# CM4_HighSpeed.net
KiCad netlist of a schematic drawn in Altium Designer
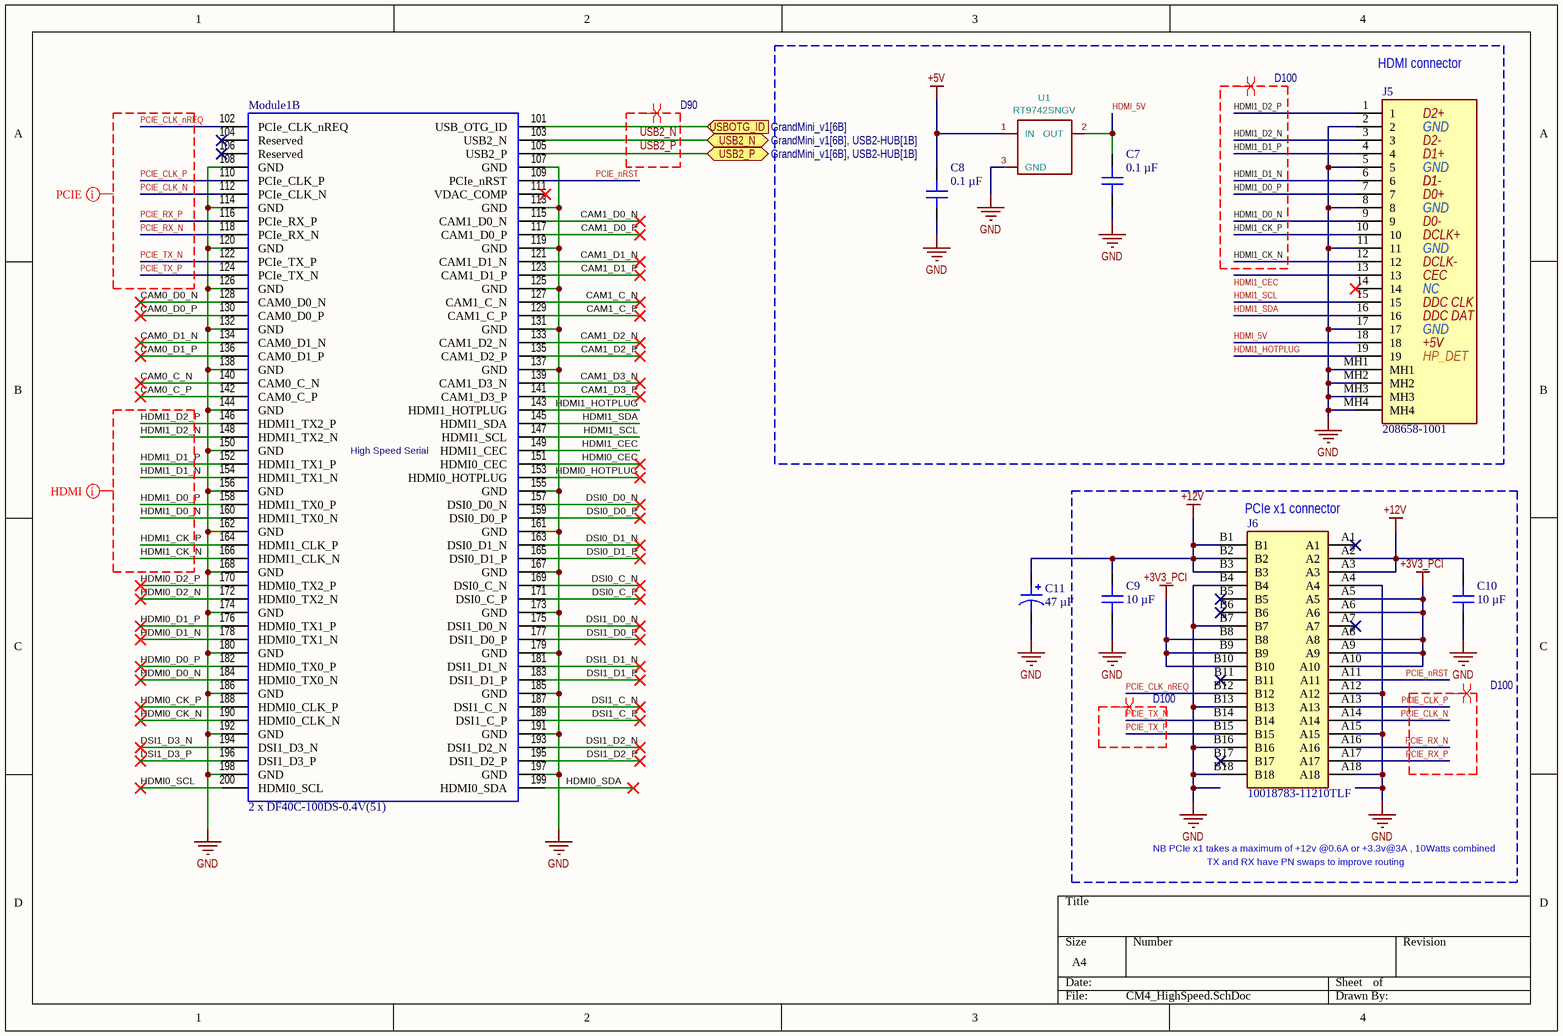
[diagram p0: CM4_HighSpeed.SchDoc]

(export (version "E")
  (design (tool "Eeschema 10.0.6"))
  (components
    (comp (ref "C7")
      (value "0.1 µF")
      (footprint "CAP 0603_1608")
      (description "CAP CER 0.1UF 50V X7R 0603")
      (fields (field (name "PART NUMBER") "CC0603KRX7R9BB104") (field (name "MANUFACTURER") "Yageo"))
      (libsource (lib "Celestial Altium Library - altium_library") (part "Capacitor"))
    )
    (comp (ref "C8")
      (value "0.1 µF")
      (footprint "CAP 0603_1608")
      (description "CAP CER 0.1UF 50V X7R 0603")
      (fields (field (name "PART NUMBER") "CC0603KRX7R9BB104") (field (name "MANUFACTURER") "Yageo"))
      (libsource (lib "Celestial Altium Library - altium_library") (part "Capacitor"))
    )
    (comp (ref "C9")
      (value "10 µF")
      (footprint "CAP 0805_2012")
      (description "CAP CER 10UF 25V X5R 0805")
      (fields (field (name "PART NUMBER") "CC0805KKX5R8BB106") (field (name "MANUFACTURER") "Yageo"))
      (libsource (lib "Celestial Altium Library - altium_library") (part "Capacitor"))
    )
    (comp (ref "C10")
      (value "10 µF")
      (footprint "CAP 0805_2012")
      (description "CAP CER 10UF 25V X5R 0805")
      (fields (field (name "PART NUMBER") "CC0805KKX5R8BB106") (field (name "MANUFACTURER") "Yageo"))
      (libsource (lib "Celestial Altium Library - altium_library") (part "Capacitor"))
    )
    (comp (ref "C11")
      (value "47 µF")
      (footprint "CAP POL 2917_7343")
      (description "CAP TANT 47UF 10% 35V 2917")
      (fields (field (name "PART NUMBER") "T491X476K035AT") (field (name "MANUFACTURER") "KEMET"))
      (libsource (lib "Celestial Altium Library - altium_library") (part "Polarised Capacitor"))
    )
    (comp (ref "J5")
      (value "208658-1001")
      (footprint "SamacSys:2086581001")
      (description "Connector, HDMI")
      (fields (field (name "MOUSER PART NUMBER") "538-208658-1001"))
      (libsource (lib "SamacSys") (part "208658-1001"))
    )
    (comp (ref "J6")
      (value "10018783-11210TLF")
      (footprint "SamacSys:1001878311210TLF")
      (description "Connector PCI-E")
      (libsource (lib "SamacSys") (part "10018783-11210TLF"))
    )
    (comp (ref "Module1")
      (value "2 x DF40C-100DS-0.4V(51)")
      (footprint "RPI_CM4_STACKED")
      (description "Rapsberry PI Compute Module 4 +")
      (libsource (lib "SamacSys") (part "RPi_CM4_1"))
    )
    (comp (ref "U1") (value "RT9742SNGV") (footprint "SOT-23") (libsource (lib "CM4IO") (part "RT9742SNGV")))
  )
  (nets
    (net (code "1") (name "+3V3_PCI") (class "Default")
      (node (ref "J6") (pin "A10") (pinfunction "A10_A10") (pintype "passive"))
      (node (ref "J6") (pin "A5") (pinfunction "A5_A5") (pintype "passive"))
      (node (ref "J6") (pin "A6") (pinfunction "A6_A6") (pintype "passive"))
      (node (ref "J6") (pin "A8") (pinfunction "A8_A8") (pintype "passive"))
      (node (ref "J6") (pin "A9") (pinfunction "A9_A9") (pintype "passive"))
      (node (ref "J6") (pin "B10") (pinfunction "B10_B10") (pintype "passive"))
      (node (ref "J6") (pin "B8") (pinfunction "B8_B8") (pintype "passive"))
      (node (ref "J6") (pin "B9") (pinfunction "B9_B9") (pintype "passive"))
    )
    (net (code "2") (name "+5V") (class "Default")
      (node (ref "C8") (pin "2") (pinfunction "2_2") (pintype "passive"))
      (node (ref "U1") (pin "1") (pinfunction "IN_1") (pintype "passive"))
    )
    (net (code "3") (name "+12V") (class "Default")
      (node (ref "C10") (pin "2") (pinfunction "2_2") (pintype "passive"))
      (node (ref "C11") (pin "1") (pinfunction "1_1") (pintype "passive"))
      (node (ref "C9") (pin "2") (pinfunction "2_2") (pintype "passive"))
      (node (ref "J6") (pin "A2") (pinfunction "A2_A2") (pintype "passive"))
      (node (ref "J6") (pin "A3") (pinfunction "A3_A3") (pintype "passive"))
      (node (ref "J6") (pin "B1") (pinfunction "B1_B1") (pintype "passive"))
      (node (ref "J6") (pin "B2") (pinfunction "B2_B2") (pintype "passive"))
      (node (ref "J6") (pin "B3") (pinfunction "B3_B3") (pintype "passive"))
    )
    (net (code "4") (name "/CAM0_C_N") (class "Default")
      (node (ref "Module1") (pin "140") (pinfunction "CAM0_C_N_140") (pintype "passive+no_connect"))
    )
    (net (code "5") (name "/CAM0_C_P") (class "Default")
      (node (ref "Module1") (pin "142") (pinfunction "CAM0_C_P_142") (pintype "passive+no_connect"))
    )
    (net (code "6") (name "/CAM0_D0_N") (class "Default")
      (node (ref "Module1") (pin "128") (pinfunction "CAM0_D0_N_128") (pintype "passive+no_connect"))
    )
    (net (code "7") (name "/CAM0_D0_P") (class "Default")
      (node (ref "Module1") (pin "130") (pinfunction "CAM0_D0_P_130") (pintype "passive+no_connect"))
    )
    (net (code "8") (name "/CAM0_D1_N") (class "Default")
      (node (ref "Module1") (pin "134") (pinfunction "CAM0_D1_N_134") (pintype "passive+no_connect"))
    )
    (net (code "9") (name "/CAM0_D1_P") (class "Default")
      (node (ref "Module1") (pin "136") (pinfunction "CAM0_D1_P_136") (pintype "passive+no_connect"))
    )
    (net (code "10") (name "/CAM1_C_N") (class "Default")
      (node (ref "Module1") (pin "127") (pinfunction "CAM1_C_N_127") (pintype "passive+no_connect"))
    )
    (net (code "11") (name "/CAM1_C_P") (class "Default")
      (node (ref "Module1") (pin "129") (pinfunction "CAM1_C_P_129") (pintype "passive+no_connect"))
    )
    (net (code "12") (name "/CAM1_D0_N") (class "Default")
      (node (ref "Module1") (pin "115") (pinfunction "CAM1_D0_N_115") (pintype "passive+no_connect"))
    )
    (net (code "13") (name "/CAM1_D0_P") (class "Default")
      (node (ref "Module1") (pin "117") (pinfunction "CAM1_D0_P_117") (pintype "passive+no_connect"))
    )
    (net (code "14") (name "/CAM1_D1_N") (class "Default")
      (node (ref "Module1") (pin "121") (pinfunction "CAM1_D1_N_121") (pintype "passive+no_connect"))
    )
    (net (code "15") (name "/CAM1_D1_P") (class "Default")
      (node (ref "Module1") (pin "123") (pinfunction "CAM1_D1_P_123") (pintype "passive+no_connect"))
    )
    (net (code "16") (name "/CAM1_D2_N") (class "Default")
      (node (ref "Module1") (pin "133") (pinfunction "CAM1_D2_N_133") (pintype "passive+no_connect"))
    )
    (net (code "17") (name "/CAM1_D2_P") (class "Default")
      (node (ref "Module1") (pin "135") (pinfunction "CAM1_D2_P_135") (pintype "passive+no_connect"))
    )
    (net (code "18") (name "/CAM1_D3_N") (class "Default")
      (node (ref "Module1") (pin "139") (pinfunction "CAM1_D3_N_139") (pintype "passive+no_connect"))
    )
    (net (code "19") (name "/CAM1_D3_P") (class "Default")
      (node (ref "Module1") (pin "141") (pinfunction "CAM1_D3_P_141") (pintype "passive+no_connect"))
    )
    (net (code "20") (name "/DSI0_C_N") (class "Default")
      (node (ref "Module1") (pin "169") (pinfunction "DSI0_C_N_169") (pintype "passive+no_connect"))
    )
    (net (code "21") (name "/DSI0_C_P") (class "Default")
      (node (ref "Module1") (pin "171") (pinfunction "DSI0_C_P_171") (pintype "passive+no_connect"))
    )
    (net (code "22") (name "/DSI0_D0_N") (class "Default")
      (node (ref "Module1") (pin "157") (pinfunction "DSI0_D0_N_157") (pintype "passive+no_connect"))
    )
    (net (code "23") (name "/DSI0_D0_P") (class "Default")
      (node (ref "Module1") (pin "159") (pinfunction "DSI0_D0_P_159") (pintype "passive+no_connect"))
    )
    (net (code "24") (name "/DSI0_D1_N") (class "Default")
      (node (ref "Module1") (pin "163") (pinfunction "DSI0_D1_N_163") (pintype "passive+no_connect"))
    )
    (net (code "25") (name "/DSI0_D1_P") (class "Default")
      (node (ref "Module1") (pin "165") (pinfunction "DSI0_D1_P_165") (pintype "passive+no_connect"))
    )
    (net (code "26") (name "/DSI1_C_N") (class "Default")
      (node (ref "Module1") (pin "187") (pinfunction "DSI1_C_N_187") (pintype "passive+no_connect"))
    )
    (net (code "27") (name "/DSI1_C_P") (class "Default")
      (node (ref "Module1") (pin "189") (pinfunction "DSI1_C_P_189") (pintype "passive+no_connect"))
    )
    (net (code "28") (name "/DSI1_D0_N") (class "Default")
      (node (ref "Module1") (pin "175") (pinfunction "DSI1_D0_N_175") (pintype "passive+no_connect"))
    )
    (net (code "29") (name "/DSI1_D0_P") (class "Default")
      (node (ref "Module1") (pin "177") (pinfunction "DSI1_D0_P_177") (pintype "passive+no_connect"))
    )
    (net (code "30") (name "/DSI1_D1_N") (class "Default")
      (node (ref "Module1") (pin "181") (pinfunction "DSI1_D1_N_181") (pintype "passive+no_connect"))
    )
    (net (code "31") (name "/DSI1_D1_P") (class "Default")
      (node (ref "Module1") (pin "183") (pinfunction "DSI1_D1_P_183") (pintype "passive+no_connect"))
    )
    (net (code "32") (name "/DSI1_D2_N") (class "Default")
      (node (ref "Module1") (pin "193") (pinfunction "DSI1_D2_N_193") (pintype "passive+no_connect"))
    )
    (net (code "33") (name "/DSI1_D2_P") (class "Default")
      (node (ref "Module1") (pin "195") (pinfunction "DSI1_D2_P_195") (pintype "passive+no_connect"))
    )
    (net (code "34") (name "/DSI1_D3_N") (class "Default")
      (node (ref "Module1") (pin "194") (pinfunction "DSI1_D3_N_194") (pintype "passive+no_connect"))
    )
    (net (code "35") (name "/DSI1_D3_P") (class "Default")
      (node (ref "Module1") (pin "196") (pinfunction "DSI1_D3_P_196") (pintype "passive+no_connect"))
    )
    (net (code "36") (name "/HDMI0_CEC") (class "Default")
      (node (ref "Module1") (pin "151") (pinfunction "HDMI0_CEC_151") (pintype "passive+no_connect"))
    )
    (net (code "37") (name "/HDMI0_CK_N") (class "Default")
      (node (ref "Module1") (pin "190") (pinfunction "HDMI0_CLK_N_190") (pintype "passive+no_connect"))
    )
    (net (code "38") (name "/HDMI0_CK_P") (class "Default")
      (node (ref "Module1") (pin "188") (pinfunction "HDMI0_CLK_P_188") (pintype "passive+no_connect"))
    )
    (net (code "39") (name "/HDMI0_D0_N") (class "Default")
      (node (ref "Module1") (pin "184") (pinfunction "HDMI0_TX0_N_184") (pintype "passive+no_connect"))
    )
    (net (code "40") (name "/HDMI0_D0_P") (class "Default")
      (node (ref "Module1") (pin "182") (pinfunction "HDMI0_TX0_P_182") (pintype "passive+no_connect"))
    )
    (net (code "41") (name "/HDMI0_D1_N") (class "Default")
      (node (ref "Module1") (pin "178") (pinfunction "HDMI0_TX1_N_178") (pintype "passive+no_connect"))
    )
    (net (code "42") (name "/HDMI0_D1_P") (class "Default")
      (node (ref "Module1") (pin "176") (pinfunction "HDMI0_TX1_P_176") (pintype "passive+no_connect"))
    )
    (net (code "43") (name "/HDMI0_D2_N") (class "Default")
      (node (ref "Module1") (pin "172") (pinfunction "HDMI0_TX2_N_172") (pintype "passive+no_connect"))
    )
    (net (code "44") (name "/HDMI0_D2_P") (class "Default")
      (node (ref "Module1") (pin "170") (pinfunction "HDMI0_TX2_P_170") (pintype "passive+no_connect"))
    )
    (net (code "45") (name "/HDMI0_HOTPLUG") (class "Default")
      (node (ref "Module1") (pin "153") (pinfunction "HDMI0_HOTPLUG_153") (pintype "passive+no_connect"))
    )
    (net (code "46") (name "/HDMI0_SCL") (class "Default")
      (node (ref "Module1") (pin "200") (pinfunction "HDMI0_SCL_200") (pintype "passive+no_connect"))
    )
    (net (code "47") (name "/HDMI0_SDA") (class "Default")
      (node (ref "Module1") (pin "199") (pinfunction "HDMI0_SDA_199") (pintype "passive+no_connect"))
    )
    (net (code "48") (name "/HDMI1_CEC") (class "Default")
      (node (ref "J5") (pin "13") (pinfunction "13_13") (pintype "passive"))
      (node (ref "Module1") (pin "149") (pinfunction "HDMI1_CEC_149") (pintype "passive"))
    )
    (net (code "49") (name "/HDMI1_CK_N") (class "Default")
      (node (ref "J5") (pin "12") (pinfunction "12_12") (pintype "passive"))
      (node (ref "Module1") (pin "166") (pinfunction "HDMI1_CLK_N_166") (pintype "passive"))
    )
    (net (code "50") (name "/HDMI1_CK_P") (class "Default")
      (node (ref "J5") (pin "10") (pinfunction "10_10") (pintype "passive"))
      (node (ref "Module1") (pin "164") (pinfunction "HDMI1_CLK_P_164") (pintype "passive"))
    )
    (net (code "51") (name "/HDMI1_D0_N") (class "Default")
      (node (ref "J5") (pin "9") (pinfunction "9_9") (pintype "passive"))
      (node (ref "Module1") (pin "160") (pinfunction "HDMI1_TX0_N_160") (pintype "passive"))
    )
    (net (code "52") (name "/HDMI1_D0_P") (class "Default")
      (node (ref "J5") (pin "7") (pinfunction "7_7") (pintype "passive"))
      (node (ref "Module1") (pin "158") (pinfunction "HDMI1_TX0_P_158") (pintype "passive"))
    )
    (net (code "53") (name "/HDMI1_D1_N") (class "Default")
      (node (ref "J5") (pin "6") (pinfunction "6_6") (pintype "passive"))
      (node (ref "Module1") (pin "154") (pinfunction "HDMI1_TX1_N_154") (pintype "passive"))
    )
    (net (code "54") (name "/HDMI1_D1_P") (class "Default")
      (node (ref "J5") (pin "4") (pinfunction "4_4") (pintype "passive"))
      (node (ref "Module1") (pin "152") (pinfunction "HDMI1_TX1_P_152") (pintype "passive"))
    )
    (net (code "55") (name "/HDMI1_D2_N") (class "Default")
      (node (ref "J5") (pin "3") (pinfunction "3_3") (pintype "passive"))
      (node (ref "Module1") (pin "148") (pinfunction "HDMI1_TX2_N_148") (pintype "passive"))
    )
    (net (code "56") (name "/HDMI1_D2_P") (class "Default")
      (node (ref "J5") (pin "1") (pinfunction "1_1") (pintype "passive"))
      (node (ref "Module1") (pin "146") (pinfunction "HDMI1_TX2_P_146") (pintype "passive"))
    )
    (net (code "57") (name "/HDMI1_HOTPLUG") (class "Default")
      (node (ref "J5") (pin "19") (pinfunction "19_19") (pintype "passive"))
      (node (ref "Module1") (pin "143") (pinfunction "HDMI1_HOTPLUG_143") (pintype "passive"))
    )
    (net (code "58") (name "/HDMI1_SCL") (class "Default")
      (node (ref "J5") (pin "15") (pinfunction "15_15") (pintype "passive"))
      (node (ref "Module1") (pin "147") (pinfunction "HDMI1_SCL_147") (pintype "passive"))
    )
    (net (code "59") (name "/HDMI1_SDA") (class "Default")
      (node (ref "J5") (pin "16") (pinfunction "16_16") (pintype "passive"))
      (node (ref "Module1") (pin "145") (pinfunction "HDMI1_SDA_145") (pintype "passive"))
    )
    (net (code "60") (name "/HDMI_5V") (class "Default")
      (node (ref "C7") (pin "2") (pinfunction "2_2") (pintype "passive"))
      (node (ref "J5") (pin "18") (pinfunction "18_18") (pintype "passive"))
      (node (ref "U1") (pin "2") (pinfunction "OUT_2") (pintype "passive"))
    )
    (net (code "61") (name "/PCIE_CLK_N") (class "Default")
      (node (ref "J6") (pin "A14") (pinfunction "A14_A14") (pintype "passive"))
      (node (ref "Module1") (pin "112") (pinfunction "PCIe_CLK_N_112") (pintype "passive"))
    )
    (net (code "62") (name "/PCIE_CLK_P") (class "Default")
      (node (ref "J6") (pin "A13") (pinfunction "A13_A13") (pintype "passive"))
      (node (ref "Module1") (pin "110") (pinfunction "PCIe_CLK_P_110") (pintype "passive"))
    )
    (net (code "63") (name "/PCIE_CLK_nREQ") (class "Default")
      (node (ref "J6") (pin "B12") (pinfunction "B12_B12") (pintype "passive"))
      (node (ref "Module1") (pin "102") (pinfunction "PCIe_CLK_nREQ_102") (pintype "passive"))
    )
    (net (code "64") (name "/PCIE_RX_N") (class "Default")
      (node (ref "J6") (pin "A16") (pinfunction "A16_A16") (pintype "passive"))
      (node (ref "Module1") (pin "118") (pinfunction "PCIe_RX_N_118") (pintype "passive"))
    )
    (net (code "65") (name "/PCIE_RX_P") (class "Default")
      (node (ref "J6") (pin "A17") (pinfunction "A17_A17") (pintype "passive"))
      (node (ref "Module1") (pin "116") (pinfunction "PCIe_RX_P_116") (pintype "passive"))
    )
    (net (code "66") (name "/PCIE_TX_N") (class "Default")
      (node (ref "J6") (pin "B14") (pinfunction "B14_B14") (pintype "passive"))
      (node (ref "Module1") (pin "122") (pinfunction "PCIe_TX_P_122") (pintype "passive"))
    )
    (net (code "67") (name "/PCIE_TX_P") (class "Default")
      (node (ref "J6") (pin "B15") (pinfunction "B15_B15") (pintype "passive"))
      (node (ref "Module1") (pin "124") (pinfunction "PCIe_TX_N_124") (pintype "passive"))
    )
    (net (code "68") (name "/PCIE_nRST") (class "Default")
      (node (ref "J6") (pin "A11") (pinfunction "A11_A11") (pintype "passive"))
      (node (ref "Module1") (pin "109") (pinfunction "PCIe_nRST_109") (pintype "passive"))
    )
    (net (code "69") (name "/USB2_N") (class "Default")
      (node (ref "Module1") (pin "103") (pinfunction "USB2_N_103") (pintype "passive"))
    )
    (net (code "70") (name "/USB2_P") (class "Default")
      (node (ref "Module1") (pin "105") (pinfunction "USB2_P_105") (pintype "passive"))
    )
    (net (code "71") (name "/USBOTG_ID") (class "Default")
      (node (ref "Module1") (pin "101") (pinfunction "USB_OTG_ID_101") (pintype "passive"))
    )
    (net (code "72") (name "GND") (class "Default")
      (node (ref "C10") (pin "1") (pinfunction "1_1") (pintype "passive"))
      (node (ref "C11") (pin "2") (pinfunction "2_2") (pintype "passive"))
      (node (ref "C7") (pin "1") (pinfunction "1_1") (pintype "passive"))
      (node (ref "C8") (pin "1") (pinfunction "1_1") (pintype "passive"))
      (node (ref "C9") (pin "1") (pinfunction "1_1") (pintype "passive"))
      (node (ref "J5") (pin "11") (pinfunction "11_11") (pintype "passive"))
      (node (ref "J5") (pin "17") (pinfunction "17_17") (pintype "passive"))
      (node (ref "J5") (pin "2") (pinfunction "2_2") (pintype "passive"))
      (node (ref "J5") (pin "5") (pinfunction "5_5") (pintype "passive"))
      (node (ref "J5") (pin "8") (pinfunction "8_8") (pintype "passive"))
      (node (ref "J5") (pin "MH1") (pinfunction "MH1_MH1") (pintype "passive"))
      (node (ref "J5") (pin "MH2") (pinfunction "MH2_MH2") (pintype "passive"))
      (node (ref "J5") (pin "MH3") (pinfunction "MH3_MH3") (pintype "passive"))
      (node (ref "J5") (pin "MH4") (pinfunction "MH4_MH4") (pintype "passive"))
      (node (ref "J6") (pin "A12") (pinfunction "A12_A12") (pintype "passive"))
      (node (ref "J6") (pin "A15") (pinfunction "A15_A15") (pintype "passive"))
      (node (ref "J6") (pin "A18") (pinfunction "A18_A18") (pintype "passive"))
      (node (ref "J6") (pin "A4") (pinfunction "A4_A4") (pintype "passive"))
      (node (ref "J6") (pin "B13") (pinfunction "B13_B13") (pintype "passive"))
      (node (ref "J6") (pin "B16") (pinfunction "B16_B16") (pintype "passive"))
      (node (ref "J6") (pin "B18") (pinfunction "B18_B18") (pintype "passive"))
      (node (ref "J6") (pin "B4") (pinfunction "B4_B4") (pintype "passive"))
      (node (ref "J6") (pin "B7") (pinfunction "B7_B7") (pintype "passive"))
      (node (ref "Module1") (pin "107") (pinfunction "GND_107") (pintype "passive"))
      (node (ref "Module1") (pin "108") (pinfunction "GND_108") (pintype "passive"))
      (node (ref "Module1") (pin "113") (pinfunction "GND_113") (pintype "passive"))
      (node (ref "Module1") (pin "114") (pinfunction "GND_114") (pintype "passive"))
      (node (ref "Module1") (pin "119") (pinfunction "GND_119") (pintype "passive"))
      (node (ref "Module1") (pin "120") (pinfunction "GND_120") (pintype "passive"))
      (node (ref "Module1") (pin "125") (pinfunction "GND_125") (pintype "passive"))
      (node (ref "Module1") (pin "126") (pinfunction "GND_126") (pintype "passive"))
      (node (ref "Module1") (pin "131") (pinfunction "GND_131") (pintype "passive"))
      (node (ref "Module1") (pin "132") (pinfunction "GND_132") (pintype "passive"))
      (node (ref "Module1") (pin "137") (pinfunction "GND_137") (pintype "passive"))
      (node (ref "Module1") (pin "138") (pinfunction "GND_138") (pintype "passive"))
      (node (ref "Module1") (pin "144") (pinfunction "GND_144") (pintype "passive"))
      (node (ref "Module1") (pin "150") (pinfunction "GND_150") (pintype "passive"))
      (node (ref "Module1") (pin "155") (pinfunction "GND_155") (pintype "passive"))
      (node (ref "Module1") (pin "156") (pinfunction "GND_156") (pintype "passive"))
      (node (ref "Module1") (pin "161") (pinfunction "GND_161") (pintype "passive"))
      (node (ref "Module1") (pin "162") (pinfunction "GND_162") (pintype "passive"))
      (node (ref "Module1") (pin "167") (pinfunction "GND_167") (pintype "passive"))
      (node (ref "Module1") (pin "168") (pinfunction "GND_168") (pintype "passive"))
      (node (ref "Module1") (pin "173") (pinfunction "GND_173") (pintype "passive"))
      (node (ref "Module1") (pin "174") (pinfunction "GND_174") (pintype "passive"))
      (node (ref "Module1") (pin "179") (pinfunction "GND_179") (pintype "passive"))
      (node (ref "Module1") (pin "180") (pinfunction "GND_180") (pintype "passive"))
      (node (ref "Module1") (pin "185") (pinfunction "GND_185") (pintype "passive"))
      (node (ref "Module1") (pin "186") (pinfunction "GND_186") (pintype "passive"))
      (node (ref "Module1") (pin "191") (pinfunction "GND_191") (pintype "passive"))
      (node (ref "Module1") (pin "192") (pinfunction "GND_192") (pintype "passive"))
      (node (ref "Module1") (pin "197") (pinfunction "GND_197") (pintype "passive"))
      (node (ref "Module1") (pin "198") (pinfunction "GND_198") (pintype "passive"))
      (node (ref "U1") (pin "3") (pinfunction "GND_3") (pintype "passive"))
    )
    (net (code "73") (name "unconnected-(J5-Pad14)") (class "Default")
      (node (ref "J5") (pin "14") (pinfunction "14_14") (pintype "passive+no_connect"))
    )
    (net (code "74") (name "unconnected-(J6-PadA1)") (class "Default")
      (node (ref "J6") (pin "A1") (pinfunction "A1_A1") (pintype "passive+no_connect"))
    )
    (net (code "75") (name "unconnected-(J6-PadA7)") (class "Default")
      (node (ref "J6") (pin "A7") (pinfunction "A7_A7") (pintype "passive+no_connect"))
    )
    (net (code "76") (name "unconnected-(J6-PadB5)") (class "Default")
      (node (ref "J6") (pin "B5") (pinfunction "B5_B5") (pintype "passive+no_connect"))
    )
    (net (code "77") (name "unconnected-(J6-PadB6)") (class "Default")
      (node (ref "J6") (pin "B6") (pinfunction "B6_B6") (pintype "passive+no_connect"))
    )
    (net (code "78") (name "unconnected-(J6-PadB11)") (class "Default")
      (node (ref "J6") (pin "B11") (pinfunction "B11_B11") (pintype "passive+no_connect"))
    )
    (net (code "79") (name "unconnected-(J6-PadB17)") (class "Default")
      (node (ref "J6") (pin "B17") (pinfunction "B17_B17") (pintype "passive+no_connect"))
    )
    (net (code "80") (name "unconnected-(Module1B-Reserved-Pad104)") (class "Default")
      (node (ref "Module1") (pin "104") (pinfunction "Reserved_104") (pintype "passive+no_connect"))
    )
    (net (code "81") (name "unconnected-(Module1B-Reserved-Pad106)") (class "Default")
      (node (ref "Module1") (pin "106") (pinfunction "Reserved_106") (pintype "passive+no_connect"))
    )
    (net (code "82") (name "unconnected-(Module1B-VDAC_COMP-Pad111)") (class "Default")
      (node (ref "Module1") (pin "111") (pinfunction "VDAC_COMP_111") (pintype "passive+no_connect"))
    )
  )
)
